# Quad_DDS.net
KiCad netlist of a schematic drawn in Altium Designer
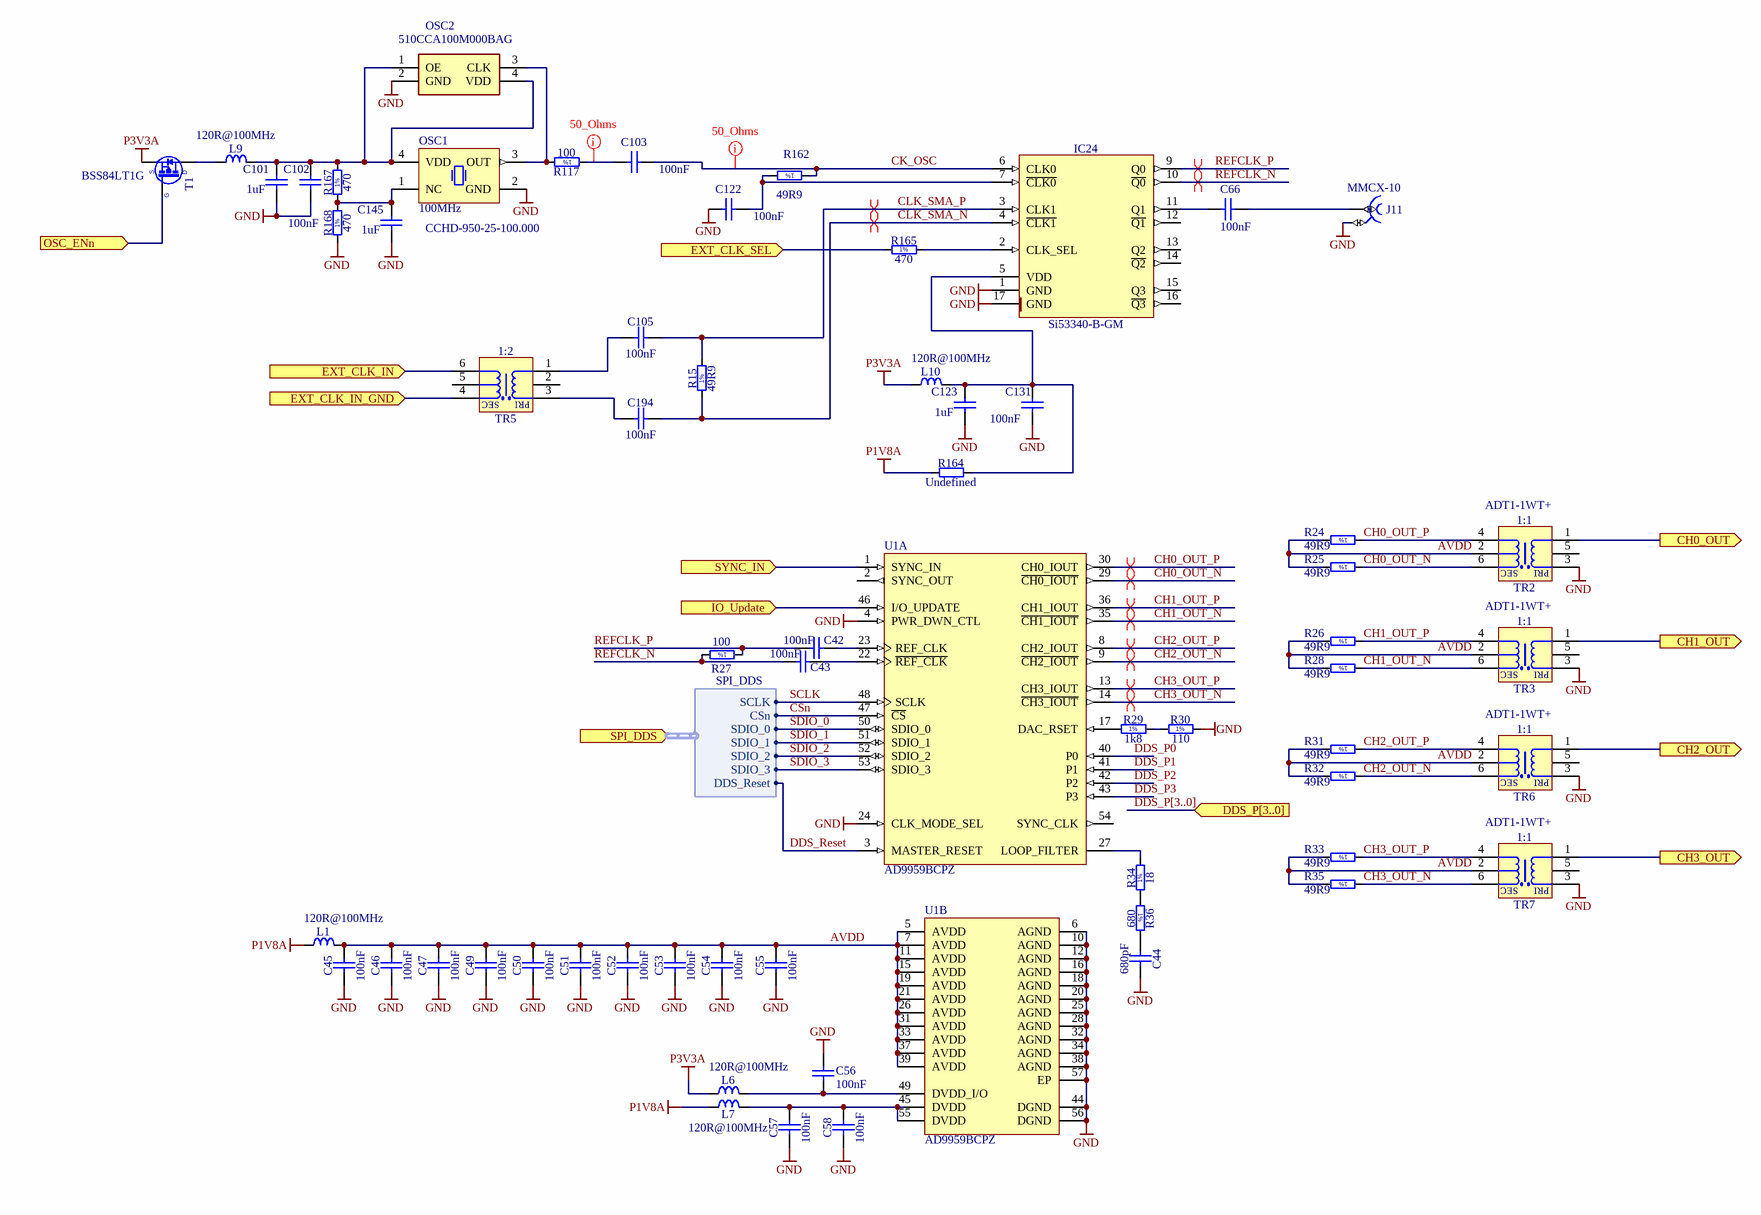
[diagram p0: Quad_DDS.SchDoc]

(export (version "E")
  (design (tool "Eeschema 10.0.6"))
  (components
    (comp (ref "C42")
      (value "100nF")
      (footprint "CAPC1005X55N")
      (description "Non-polarised capacitor")
      (fields
        (field (name "PART NUMBER") "CC0402_100NF_16V_10%_X5R")
        (field (name "VOLTAGE") "16V")
        (field (name "AUTHOR") "CERN DEM JLC")
      )
      (libsource (lib "Capacitors") (part "Capacitor - non polarized"))
    )
    (comp (ref "C43")
      (value "100nF")
      (footprint "CAPC1005X55N")
      (description "Non-polarised capacitor")
      (fields
        (field (name "PART NUMBER") "CC0402_100NF_16V_10%_X5R")
        (field (name "VOLTAGE") "16V")
        (field (name "AUTHOR") "CERN DEM JLC")
      )
      (libsource (lib "Capacitors") (part "Capacitor - non polarized"))
    )
    (comp (ref "C44")
      (value "680pF")
      (footprint "CAPC1608X87N")
      (description "Non-polarised capacitor")
      (fields
        (field (name "PART NUMBER") "CC0603_680PF_50V_5%_NP0")
        (field (name "VOLTAGE") "50V")
        (field (name "AUTHOR") "CERN DEM JLC")
      )
      (libsource (lib "Capacitors") (part "Capacitor - non polarized"))
    )
    (comp (ref "C45")
      (value "100nF")
      (footprint "CAPC1005X55N")
      (description "Non-polarised capacitor")
      (fields
        (field (name "PART NUMBER") "CC0402_100NF_16V_10%_X5R")
        (field (name "VOLTAGE") "16V")
        (field (name "AUTHOR") "CERN DEM JLC")
      )
      (libsource (lib "Capacitors") (part "Capacitor - non polarized"))
    )
    (comp (ref "C46")
      (value "100nF")
      (footprint "CAPC1005X55N")
      (description "Non-polarised capacitor")
      (fields
        (field (name "PART NUMBER") "CC0402_100NF_16V_10%_X5R")
        (field (name "VOLTAGE") "16V")
        (field (name "AUTHOR") "CERN DEM JLC")
      )
      (libsource (lib "Capacitors") (part "Capacitor - non polarized"))
    )
    (comp (ref "C47")
      (value "100nF")
      (footprint "CAPC1005X55N")
      (description "Non-polarised capacitor")
      (fields
        (field (name "PART NUMBER") "CC0402_100NF_16V_10%_X5R")
        (field (name "VOLTAGE") "16V")
        (field (name "AUTHOR") "CERN DEM JLC")
      )
      (libsource (lib "Capacitors") (part "Capacitor - non polarized"))
    )
    (comp (ref "C49")
      (value "100nF")
      (footprint "CAPC1005X55N")
      (description "Non-polarised capacitor")
      (fields
        (field (name "PART NUMBER") "CC0402_100NF_16V_10%_X5R")
        (field (name "VOLTAGE") "16V")
        (field (name "AUTHOR") "CERN DEM JLC")
      )
      (libsource (lib "Capacitors") (part "Capacitor - non polarized"))
    )
    (comp (ref "C50")
      (value "100nF")
      (footprint "CAPC1005X55N")
      (description "Non-polarised capacitor")
      (fields
        (field (name "PART NUMBER") "CC0402_100NF_16V_10%_X5R")
        (field (name "VOLTAGE") "16V")
        (field (name "AUTHOR") "CERN DEM JLC")
      )
      (libsource (lib "Capacitors") (part "Capacitor - non polarized"))
    )
    (comp (ref "C51")
      (value "100nF")
      (footprint "CAPC1005X55N")
      (description "Non-polarised capacitor")
      (fields
        (field (name "PART NUMBER") "CC0402_100NF_16V_10%_X5R")
        (field (name "VOLTAGE") "16V")
        (field (name "AUTHOR") "CERN DEM JLC")
      )
      (libsource (lib "Capacitors") (part "Capacitor - non polarized"))
    )
    (comp (ref "C52")
      (value "100nF")
      (footprint "CAPC1005X55N")
      (description "Non-polarised capacitor")
      (fields
        (field (name "PART NUMBER") "CC0402_100NF_16V_10%_X5R")
        (field (name "VOLTAGE") "16V")
        (field (name "AUTHOR") "CERN DEM JLC")
      )
      (libsource (lib "Capacitors") (part "Capacitor - non polarized"))
    )
    (comp (ref "C53")
      (value "100nF")
      (footprint "CAPC1005X55N")
      (description "Non-polarised capacitor")
      (fields
        (field (name "PART NUMBER") "CC0402_100NF_16V_10%_X5R")
        (field (name "VOLTAGE") "16V")
        (field (name "AUTHOR") "CERN DEM JLC")
      )
      (libsource (lib "Capacitors") (part "Capacitor - non polarized"))
    )
    (comp (ref "C54")
      (value "100nF")
      (footprint "CAPC1005X55N")
      (description "Non-polarised capacitor")
      (fields
        (field (name "PART NUMBER") "CC0402_100NF_16V_10%_X5R")
        (field (name "VOLTAGE") "16V")
        (field (name "AUTHOR") "CERN DEM JLC")
      )
      (libsource (lib "Capacitors") (part "Capacitor - non polarized"))
    )
    (comp (ref "C55")
      (value "100nF")
      (footprint "CAPC1005X55N")
      (description "Non-polarised capacitor")
      (fields
        (field (name "PART NUMBER") "CC0402_100NF_16V_10%_X5R")
        (field (name "VOLTAGE") "16V")
        (field (name "AUTHOR") "CERN DEM JLC")
      )
      (libsource (lib "Capacitors") (part "Capacitor - non polarized"))
    )
    (comp (ref "C56")
      (value "100nF")
      (footprint "CAPC1005X55N")
      (description "Non-polarised capacitor")
      (fields
        (field (name "PART NUMBER") "CC0402_100NF_16V_10%_X5R")
        (field (name "VOLTAGE") "16V")
        (field (name "AUTHOR") "CERN DEM JLC")
      )
      (libsource (lib "Capacitors") (part "Capacitor - non polarized"))
    )
    (comp (ref "C57")
      (value "100nF")
      (footprint "CAPC1005X55N")
      (description "Non-polarised capacitor")
      (fields
        (field (name "PART NUMBER") "CC0402_100NF_16V_10%_X5R")
        (field (name "VOLTAGE") "16V")
        (field (name "AUTHOR") "CERN DEM JLC")
      )
      (libsource (lib "Capacitors") (part "Capacitor - non polarized"))
    )
    (comp (ref "C58")
      (value "100nF")
      (footprint "CAPC1005X55N")
      (description "Non-polarised capacitor")
      (fields
        (field (name "PART NUMBER") "CC0402_100NF_16V_10%_X5R")
        (field (name "VOLTAGE") "16V")
        (field (name "AUTHOR") "CERN DEM JLC")
      )
      (libsource (lib "Capacitors") (part "Capacitor - non polarized"))
    )
    (comp (ref "C66")
      (value "100nF")
      (footprint "CAPC1005X55N")
      (description "Non-polarised capacitor")
      (fields
        (field (name "PART NUMBER") "CC0402_100NF_16V_10%_X5R")
        (field (name "VOLTAGE") "16V")
        (field (name "AUTHOR") "CERN DEM JLC")
      )
      (libsource (lib "Capacitors") (part "Capacitor - non polarized"))
    )
    (comp (ref "C101")
      (value "1uF")
      (footprint "CAPC1005X55N")
      (description "Non-polarised capacitor")
      (fields
        (field (name "PART NUMBER") "CC0402_1UF_16V_10%_X5R")
        (field (name "VOLTAGE") "16V")
        (field (name "AUTHOR") "CERN DEM JLC")
      )
      (libsource (lib "Capacitors") (part "Capacitor - non polarized"))
    )
    (comp (ref "C102")
      (value "100nF")
      (footprint "CAPC1005X55N")
      (description "Non-polarised capacitor")
      (fields
        (field (name "PART NUMBER") "CC0402_100NF_16V_10%_X5R")
        (field (name "VOLTAGE") "16V")
        (field (name "AUTHOR") "CERN DEM JLC")
      )
      (libsource (lib "Capacitors") (part "Capacitor - non polarized"))
    )
    (comp (ref "C103")
      (value "100nF")
      (footprint "CAPC1005X55N")
      (description "Non-polarised capacitor")
      (fields
        (field (name "PART NUMBER") "CC0402_100NF_16V_10%_X5R")
        (field (name "VOLTAGE") "16V")
        (field (name "AUTHOR") "CERN DEM JLC")
      )
      (libsource (lib "Capacitors") (part "Capacitor - non polarized"))
    )
    (comp (ref "C105")
      (value "100nF")
      (footprint "CAPC1005X55N")
      (description "Non-polarised capacitor")
      (fields
        (field (name "PART NUMBER") "CC0402_100NF_16V_10%_X5R")
        (field (name "VOLTAGE") "16V")
        (field (name "AUTHOR") "CERN DEM JLC")
      )
      (libsource (lib "Capacitors") (part "Capacitor - non polarized"))
    )
    (comp (ref "C122")
      (value "100nF")
      (footprint "CAPC1005X55N")
      (description "Non-polarised capacitor")
      (fields
        (field (name "PART NUMBER") "CC0402_100NF_16V_10%_X5R")
        (field (name "VOLTAGE") "16V")
        (field (name "AUTHOR") "CERN DEM JLC")
      )
      (libsource (lib "Capacitors") (part "Capacitor - non polarized"))
    )
    (comp (ref "C123")
      (value "1uF")
      (footprint "CAPC1005X55N")
      (description "Non-polarised capacitor")
      (fields
        (field (name "PART NUMBER") "CC0402_1UF_16V_10%_X5R")
        (field (name "VOLTAGE") "16V")
        (field (name "AUTHOR") "CERN DEM JLC")
      )
      (libsource (lib "Capacitors") (part "Capacitor - non polarized"))
    )
    (comp (ref "C131")
      (value "100nF")
      (footprint "CAPC1005X55N")
      (description "Non-polarised capacitor")
      (fields
        (field (name "PART NUMBER") "CC0402_100NF_16V_10%_X5R")
        (field (name "VOLTAGE") "16V")
        (field (name "AUTHOR") "CERN DEM JLC")
      )
      (libsource (lib "Capacitors") (part "Capacitor - non polarized"))
    )
    (comp (ref "C145")
      (value "1uF")
      (footprint "CAPC1005X55N")
      (description "Non-polarised capacitor")
      (fields
        (field (name "PART NUMBER") "CC0402_1UF_16V_10%_X5R")
        (field (name "VOLTAGE") "16V")
        (field (name "AUTHOR") "CERN DEM JLC")
      )
      (libsource (lib "Capacitors") (part "Capacitor - non polarized"))
    )
    (comp (ref "C194")
      (value "100nF")
      (footprint "CAPC1005X55N")
      (description "Non-polarised capacitor")
      (fields
        (field (name "PART NUMBER") "CC0402_100NF_16V_10%_X5R")
        (field (name "VOLTAGE") "16V")
        (field (name "AUTHOR") "CERN DEM JLC")
      )
      (libsource (lib "Capacitors") (part "Capacitor - non polarized"))
    )
    (comp (ref "IC24")
      (value "Si53340-B-GM")
      (footprint "QFN50P300X300X90-17N-S175")
      (description "Low-Jitter LVDS Fanout Clock Buffers, 10-Output,  Any-Input, Any-Frequency up to 1250MHz")
      (fields (field (name "MANUFACTURER") "SILICON LABS") (field (name "AUTHOR") "CERN DEM MR"))
      (libsource (lib "ICs And Semiconductors") (part "Si53340"))
    )
    (comp (ref "J11")
      (value "Coax_1Female_1Shield")
      (footprint "NINIGI_MMCX-10")
      (fields
        (field (name "PART NUMBER") "MMCX-10")
        (field (name "MANUFACTURER") "NINIGI")
        (field (name "MANUFACTURER PART NUMBER") "NINIGI MMCX-10")
        (field (name "AUTHOR") "GK")
      )
      (libsource (lib "Connectors") (part "CON_RF_MMCX"))
    )
    (comp (ref "L1")
      (value "120R@100MHz")
      (footprint "INDC1608X95N")
      (description "Inductor")
      (fields
        (field (name "PART NUMBER") "IND0603_MURATA_BLM18PG121SN1D")
        (field (name "POWER") "2A")
        (field (name "AUTHOR") "CERN DEM BC")
      )
      (libsource (lib "Inductors & Transformers") (part "Inductor"))
    )
    (comp (ref "L6")
      (value "120R@100MHz")
      (footprint "INDC1608X95N")
      (description "Inductor")
      (fields
        (field (name "PART NUMBER") "IND0603_MURATA_BLM18PG121SN1D")
        (field (name "POWER") "2A")
        (field (name "AUTHOR") "CERN DEM BC")
      )
      (libsource (lib "Inductors & Transformers") (part "Inductor"))
    )
    (comp (ref "L7")
      (value "120R@100MHz")
      (footprint "INDC1608X95N")
      (description "Inductor")
      (fields
        (field (name "PART NUMBER") "IND0603_MURATA_BLM18PG121SN1D")
        (field (name "POWER") "2A")
        (field (name "AUTHOR") "CERN DEM BC")
      )
      (libsource (lib "Inductors & Transformers") (part "Inductor"))
    )
    (comp (ref "L9")
      (value "120R@100MHz")
      (footprint "INDC1608X95N")
      (description "Inductor")
      (fields
        (field (name "PART NUMBER") "IND0603_MURATA_BLM18PG121SN1D")
        (field (name "POWER") "2A")
        (field (name "AUTHOR") "CERN DEM BC")
      )
      (libsource (lib "Inductors & Transformers") (part "Inductor"))
    )
    (comp (ref "L10")
      (value "120R@100MHz")
      (footprint "INDC1608X95N")
      (description "Inductor")
      (fields
        (field (name "PART NUMBER") "IND0603_MURATA_BLM18PG121SN1D")
        (field (name "POWER") "2A")
        (field (name "AUTHOR") "CERN DEM BC")
      )
      (libsource (lib "Inductors & Transformers") (part "Inductor"))
    )
    (comp (ref "OSC1")
      (value "100MHz")
      (footprint "OSC_CRYSTEK_CCHD-950")
      (description "100MHz low noise oscillator")
      (fields
        (field (name "PART NUMBER") "OSC_100MHZ_CRYSTEK_CCHD-950-25-100.000")
        (field (name "MANUFACTURER") "CRYSTEK CRYSTAL")
        (field (name "MANUFACTURER PART NUMBER") "CCHD-950-25-100.000")
        (field (name "AUTHOR") "GK")
      )
      (libsource (lib "LIBRARY_SCH") (part "OSC_CCHD-950"))
    )
    (comp (ref "OSC2")
      (value "510CCA100M000BAG")
      (footprint "SamacSys:510CBA49M1520BAG")
      (description "Crystal or Oscillator")
      (fields (field (name "MOUSER PART NUMBER") "634-510CCA100M000BAG"))
      (libsource (lib "*") (part "510CCA100M000BAG"))
    )
    (comp (ref "R15")
      (value "49R9")
      (footprint "RESC1005X40N")
      (description "Resistor - 1%")
      (fields
        (field (name "PART NUMBER") "R0402_49R9_1%_0.0625W_100PPM")
        (field (name "POWER") "0.0625W")
        (field (name "AUTHOR") "CERN DEM JLC")
      )
      (libsource (lib "Resistors") (part "Resistor - 1%"))
    )
    (comp (ref "R24")
      (value "49R9")
      (footprint "RESC1005X40N")
      (description "Resistor - 1%")
      (fields
        (field (name "PART NUMBER") "R0402_49R9_1%_0.0625W_100PPM")
        (field (name "POWER") "0.0625W")
        (field (name "AUTHOR") "CERN DEM JLC")
      )
      (libsource (lib "Resistors") (part "Resistor - 1%"))
    )
    (comp (ref "R25")
      (value "49R9")
      (footprint "RESC1005X40N")
      (description "Resistor - 1%")
      (fields
        (field (name "PART NUMBER") "R0402_49R9_1%_0.0625W_100PPM")
        (field (name "POWER") "0.0625W")
        (field (name "AUTHOR") "CERN DEM JLC")
      )
      (libsource (lib "Resistors") (part "Resistor - 1%"))
    )
    (comp (ref "R26")
      (value "49R9")
      (footprint "RESC1005X40N")
      (description "Resistor - 1%")
      (fields
        (field (name "PART NUMBER") "R0402_49R9_1%_0.0625W_100PPM")
        (field (name "POWER") "0.0625W")
        (field (name "AUTHOR") "CERN DEM JLC")
      )
      (libsource (lib "Resistors") (part "Resistor - 1%"))
    )
    (comp (ref "R27")
      (value "100")
      (footprint "RESC1005X40N")
      (description "Resistor - 1%")
      (fields
        (field (name "PART NUMBER") "R0402_100R_1%_0.0625W_100PPM")
        (field (name "POWER") "0.0625W")
        (field (name "AUTHOR") "CERN DEM JLC")
      )
      (libsource (lib "Resistors") (part "Resistor - 1%"))
    )
    (comp (ref "R28")
      (value "49R9")
      (footprint "RESC1005X40N")
      (description "Resistor - 1%")
      (fields
        (field (name "PART NUMBER") "R0402_49R9_1%_0.0625W_100PPM")
        (field (name "POWER") "0.0625W")
        (field (name "AUTHOR") "CERN DEM JLC")
      )
      (libsource (lib "Resistors") (part "Resistor - 1%"))
    )
    (comp (ref "R29")
      (value "1k8")
      (footprint "RESC1608X55N")
      (description "Resistor - 1%")
      (fields
        (field (name "PART NUMBER") "R0603_1K8_1%_0.1W_100PPM")
        (field (name "POWER") "0.1W")
        (field (name "AUTHOR") "CERN DEM JLC")
      )
      (libsource (lib "Resistors") (part "Resistor - 1%"))
    )
    (comp (ref "R30")
      (value "110")
      (footprint "RESC1005X40N")
      (description "Resistor - 1%")
      (fields
        (field (name "PART NUMBER") "R0402_110R_1%_0.0625W_100PPM")
        (field (name "POWER") "0.0625W")
        (field (name "AUTHOR") "CERN DEM JLC")
      )
      (libsource (lib "Resistors") (part "Resistor - 1%"))
    )
    (comp (ref "R31")
      (value "49R9")
      (footprint "RESC1005X40N")
      (description "Resistor - 1%")
      (fields
        (field (name "PART NUMBER") "R0402_49R9_1%_0.0625W_100PPM")
        (field (name "POWER") "0.0625W")
        (field (name "AUTHOR") "CERN DEM JLC")
      )
      (libsource (lib "Resistors") (part "Resistor - 1%"))
    )
    (comp (ref "R32")
      (value "49R9")
      (footprint "RESC1005X40N")
      (description "Resistor - 1%")
      (fields
        (field (name "PART NUMBER") "R0402_49R9_1%_0.0625W_100PPM")
        (field (name "POWER") "0.0625W")
        (field (name "AUTHOR") "CERN DEM JLC")
      )
      (libsource (lib "Resistors") (part "Resistor - 1%"))
    )
    (comp (ref "R33")
      (value "49R9")
      (footprint "RESC1005X40N")
      (description "Resistor - 1%")
      (fields
        (field (name "PART NUMBER") "R0402_49R9_1%_0.0625W_100PPM")
        (field (name "POWER") "0.0625W")
        (field (name "AUTHOR") "CERN DEM JLC")
      )
      (libsource (lib "Resistors") (part "Resistor - 1%"))
    )
    (comp (ref "R34")
      (value "18")
      (footprint "RESC1005X40N")
      (description "Resistor - 1%")
      (fields
        (field (name "PART NUMBER") "R0402_18R_1%_0.0625W_100PPM")
        (field (name "POWER") "0.0625W")
        (field (name "AUTHOR") "CERN DEM JLC")
      )
      (libsource (lib "Resistors") (part "Resistor - 1%"))
    )
    (comp (ref "R35")
      (value "49R9")
      (footprint "RESC1005X40N")
      (description "Resistor - 1%")
      (fields
        (field (name "PART NUMBER") "R0402_49R9_1%_0.0625W_100PPM")
        (field (name "POWER") "0.0625W")
        (field (name "AUTHOR") "CERN DEM JLC")
      )
      (libsource (lib "Resistors") (part "Resistor - 1%"))
    )
    (comp (ref "R36")
      (value "680")
      (footprint "RESC1005X40N")
      (description "Resistor - 1%")
      (fields
        (field (name "PART NUMBER") "R0402_680R_1%_0.0625W_100PPM")
        (field (name "POWER") "0.0625W")
        (field (name "AUTHOR") "CERN DEM JLC")
      )
      (libsource (lib "Resistors") (part "Resistor - 1%"))
    )
    (comp (ref "R117")
      (value "100")
      (footprint "RESC1005X40N")
      (description "Resistor - 1%")
      (fields
        (field (name "PART NUMBER") "R0402_100R_1%_0.0625W_100PPM")
        (field (name "POWER") "0.0625W")
        (field (name "AUTHOR") "CERN DEM JLC")
      )
      (libsource (lib "Resistors") (part "Resistor - 1%"))
    )
    (comp (ref "R162")
      (value "49R9")
      (footprint "RESC1005X40N")
      (description "Resistor - 1%")
      (fields
        (field (name "PART NUMBER") "R0402_49R9_1%_0.0625W_100PPM")
        (field (name "POWER") "0.0625W")
        (field (name "AUTHOR") "CERN DEM JLC")
      )
      (libsource (lib "Resistors") (part "Resistor - 1%"))
    )
    (comp (ref "R164")
      (value "Undefined")
      (footprint "RESC1608X55N")
      (description "Resistor")
      (fields (field (name "PART NUMBER") "R0603_NO-VALUE") (field (name "AUTHOR") "CERN DEM JLC"))
      (libsource (lib "Resistors") (part "Resistor"))
    )
    (comp (ref "R165")
      (value "470")
      (footprint "RESC1005X40N")
      (description "Resistor - 1%")
      (fields
        (field (name "PART NUMBER") "R0402_470R_1%_0.0625W_100PPM")
        (field (name "POWER") "0.0625W")
        (field (name "AUTHOR") "CERN DEM JLC")
      )
      (libsource (lib "Resistors") (part "Resistor - 1%"))
    )
    (comp (ref "R167")
      (value "470")
      (footprint "RESC1005X40N")
      (description "Resistor - 1%")
      (fields
        (field (name "PART NUMBER") "R0402_470R_1%_0.0625W_100PPM")
        (field (name "POWER") "0.0625W")
        (field (name "AUTHOR") "CERN DEM JLC")
      )
      (libsource (lib "Resistors") (part "Resistor - 1%"))
    )
    (comp (ref "R168")
      (value "470")
      (footprint "RESC1005X40N")
      (description "Resistor - 1%")
      (fields
        (field (name "PART NUMBER") "R0402_470R_1%_0.0625W_100PPM")
        (field (name "POWER") "0.0625W")
        (field (name "AUTHOR") "CERN DEM JLC")
      )
      (libsource (lib "Resistors") (part "Resistor - 1%"))
    )
    (comp (ref "T1")
      (value "BSS84LT1G")
      (footprint "SOT95P240X110-3N")
      (description "P-CHANNEL MOSFET WITH DIODE")
      (fields (field (name "MANUFACTURER") "ON SEMICONDUCTOR") (field (name "AUTHOR") "CERN DEM JLC"))
      (libsource (lib "ICs And Semiconductors") (part "P-MOSFET-D 1G 2S 3D"))
    )
    (comp (ref "TR2")
      (value "1:1")
      (footprint "XFMR_MINI-CIRCUITS_CD542")
      (description "75 Ohm 0.4 To 800MHz RF Transformers")
      (fields
        (field (name "PART NUMBER") "XFMR_MINI-CIRCUITS_ADT1-1WT+")
        (field (name "MANUFACTURER") "MINI-CIRCUITS")
        (field (name "MANUFACTURER PART NUMBER") "ADT1-1WT+")
        (field (name "AUTHOR") "CERN DEM JLC")
      )
      (libsource (lib "Inductors & Transformers") (part "XFMR_MINI-CIRCUITS_ADT1-1WT+"))
    )
    (comp (ref "TR3")
      (value "1:1")
      (footprint "XFMR_MINI-CIRCUITS_CD542")
      (description "75 Ohm 0.4 To 800MHz RF Transformers")
      (fields
        (field (name "PART NUMBER") "XFMR_MINI-CIRCUITS_ADT1-1WT+")
        (field (name "MANUFACTURER") "MINI-CIRCUITS")
        (field (name "MANUFACTURER PART NUMBER") "ADT1-1WT+")
        (field (name "AUTHOR") "CERN DEM JLC")
      )
      (libsource (lib "Inductors & Transformers") (part "XFMR_MINI-CIRCUITS_ADT1-1WT+"))
    )
    (comp (ref "TR5")
      (value "1:2")
      (footprint "XFMR_MINI-CIRCUITS_CD542")
      (description "50 Ohms 0.4 To 450MHz RF Transformer")
      (fields
        (field (name "PART NUMBER") "XFMR_MINI-CIRCUITS_ADT2-1T+")
        (field (name "MANUFACTURER") "MINI-CIRCUITS")
        (field (name "AUTHOR") "CERN DEM MR")
      )
      (libsource (lib "Inductors & Transformers") (part "XFMR_MINI-CIRCUITS_ADT2-1T-1P+"))
    )
    (comp (ref "TR6")
      (value "1:1")
      (footprint "XFMR_MINI-CIRCUITS_CD542")
      (description "75 Ohm 0.4 To 800MHz RF Transformers")
      (fields
        (field (name "PART NUMBER") "XFMR_MINI-CIRCUITS_ADT1-1WT+")
        (field (name "MANUFACTURER") "MINI-CIRCUITS")
        (field (name "MANUFACTURER PART NUMBER") "ADT1-1WT+")
        (field (name "AUTHOR") "CERN DEM JLC")
      )
      (libsource (lib "Inductors & Transformers") (part "XFMR_MINI-CIRCUITS_ADT1-1WT+"))
    )
    (comp (ref "TR7")
      (value "1:1")
      (footprint "XFMR_MINI-CIRCUITS_CD542")
      (description "75 Ohm 0.4 To 800MHz RF Transformers")
      (fields
        (field (name "PART NUMBER") "XFMR_MINI-CIRCUITS_ADT1-1WT+")
        (field (name "MANUFACTURER") "MINI-CIRCUITS")
        (field (name "MANUFACTURER PART NUMBER") "ADT1-1WT+")
        (field (name "AUTHOR") "CERN DEM JLC")
      )
      (libsource (lib "Inductors & Transformers") (part "XFMR_MINI-CIRCUITS_ADT1-1WT+"))
    )
    (comp (ref "U1")
      (value "AD9959BCPZ")
      (footprint "ADI-CP-56-1_M")
      (description "4-Channel, 500 MSPS DDS with 10-Bit DACs, Serial, CP-56-1, 260 Tray, Pb-Free")
      (libsource (lib "Altium Content Vault") (part "ADI-AD9959-CP-56-1"))
    )
  )
  (nets
    (net (code "2") (name "/AVDD") (class "Default")
      (node (ref "C45") (pin "2") (pinfunction "2_2") (pintype "passive"))
      (node (ref "C46") (pin "2") (pinfunction "2_2") (pintype "passive"))
      (node (ref "C47") (pin "2") (pinfunction "2_2") (pintype "passive"))
      (node (ref "C49") (pin "2") (pinfunction "2_2") (pintype "passive"))
      (node (ref "C50") (pin "2") (pinfunction "2_2") (pintype "passive"))
      (node (ref "C51") (pin "2") (pinfunction "2_2") (pintype "passive"))
      (node (ref "C52") (pin "2") (pinfunction "2_2") (pintype "passive"))
      (node (ref "C53") (pin "2") (pinfunction "2_2") (pintype "passive"))
      (node (ref "C54") (pin "2") (pinfunction "2_2") (pintype "passive"))
      (node (ref "C55") (pin "2") (pinfunction "2_2") (pintype "passive"))
      (node (ref "L1") (pin "1") (pinfunction "1_1") (pintype "passive"))
      (node (ref "R24") (pin "2") (pinfunction "2_2") (pintype "passive"))
      (node (ref "R25") (pin "2") (pinfunction "2_2") (pintype "passive"))
      (node (ref "R26") (pin "2") (pinfunction "2_2") (pintype "passive"))
      (node (ref "R28") (pin "2") (pinfunction "2_2") (pintype "passive"))
      (node (ref "R31") (pin "2") (pinfunction "2_2") (pintype "passive"))
      (node (ref "R32") (pin "2") (pinfunction "2_2") (pintype "passive"))
      (node (ref "R33") (pin "2") (pinfunction "2_2") (pintype "passive"))
      (node (ref "R35") (pin "2") (pinfunction "2_2") (pintype "passive"))
      (node (ref "TR2") (pin "2") (pinfunction "SCT_2") (pintype "passive"))
      (node (ref "TR3") (pin "2") (pinfunction "SCT_2") (pintype "passive"))
      (node (ref "TR6") (pin "2") (pinfunction "SCT_2") (pintype "passive"))
      (node (ref "TR7") (pin "2") (pinfunction "SCT_2") (pintype "passive"))
      (node (ref "U1") (pin "11") (pinfunction "AVDD_11") (pintype "power_in"))
      (node (ref "U1") (pin "15") (pinfunction "AVDD_15") (pintype "power_in"))
      (node (ref "U1") (pin "19") (pinfunction "AVDD_19") (pintype "power_in"))
      (node (ref "U1") (pin "21") (pinfunction "AVDD_21") (pintype "power_in"))
      (node (ref "U1") (pin "26") (pinfunction "AVDD_26") (pintype "power_in"))
      (node (ref "U1") (pin "31") (pinfunction "AVDD_31") (pintype "power_in"))
      (node (ref "U1") (pin "33") (pinfunction "AVDD_33") (pintype "power_in"))
      (node (ref "U1") (pin "37") (pinfunction "AVDD_37") (pintype "power_in"))
      (node (ref "U1") (pin "39") (pinfunction "AVDD_39") (pintype "power_in"))
      (node (ref "U1") (pin "5") (pinfunction "AVDD_5") (pintype "power_in"))
      (node (ref "U1") (pin "7") (pinfunction "AVDD_7") (pintype "power_in"))
    )
    (net (code "3") (name "/CH0_OUT") (class "Default")
      (node (ref "TR2") (pin "1") (pinfunction "P_1") (pintype "passive"))
    )
    (net (code "4") (name "/CH0_OUT_N") (class "Default")
      (node (ref "R25") (pin "1") (pinfunction "1_1") (pintype "passive"))
      (node (ref "TR2") (pin "6") (pinfunction "SDOT_6") (pintype "passive"))
      (node (ref "U1") (pin "29") (pinfunction "~{CH0_IOUT}_29") (pintype "output"))
    )
    (net (code "5") (name "/CH0_OUT_P") (class "Default")
      (node (ref "R24") (pin "1") (pinfunction "1_1") (pintype "passive"))
      (node (ref "TR2") (pin "4") (pinfunction "S_4") (pintype "passive"))
      (node (ref "U1") (pin "30") (pinfunction "CH0_IOUT_30") (pintype "output"))
    )
    (net (code "6") (name "/CH1_OUT") (class "Default")
      (node (ref "TR3") (pin "1") (pinfunction "P_1") (pintype "passive"))
    )
    (net (code "7") (name "/CH1_OUT_N") (class "Default")
      (node (ref "R28") (pin "1") (pinfunction "1_1") (pintype "passive"))
      (node (ref "TR3") (pin "6") (pinfunction "SDOT_6") (pintype "passive"))
      (node (ref "U1") (pin "35") (pinfunction "~{CH1_IOUT}_35") (pintype "output"))
    )
    (net (code "8") (name "/CH1_OUT_P") (class "Default")
      (node (ref "R26") (pin "1") (pinfunction "1_1") (pintype "passive"))
      (node (ref "TR3") (pin "4") (pinfunction "S_4") (pintype "passive"))
      (node (ref "U1") (pin "36") (pinfunction "CH1_IOUT_36") (pintype "output"))
    )
    (net (code "9") (name "/CH2_OUT") (class "Default")
      (node (ref "TR6") (pin "1") (pinfunction "P_1") (pintype "passive"))
    )
    (net (code "10") (name "/CH2_OUT_N") (class "Default")
      (node (ref "R32") (pin "1") (pinfunction "1_1") (pintype "passive"))
      (node (ref "TR6") (pin "6") (pinfunction "SDOT_6") (pintype "passive"))
      (node (ref "U1") (pin "9") (pinfunction "~{CH2_IOUT}_9") (pintype "output"))
    )
    (net (code "11") (name "/CH2_OUT_P") (class "Default")
      (node (ref "R31") (pin "1") (pinfunction "1_1") (pintype "passive"))
      (node (ref "TR6") (pin "4") (pinfunction "S_4") (pintype "passive"))
      (node (ref "U1") (pin "8") (pinfunction "CH2_IOUT_8") (pintype "output"))
    )
    (net (code "12") (name "/CH3_OUT") (class "Default")
      (node (ref "TR7") (pin "1") (pinfunction "P_1") (pintype "passive"))
    )
    (net (code "13") (name "/CH3_OUT_N") (class "Default")
      (node (ref "R35") (pin "1") (pinfunction "1_1") (pintype "passive"))
      (node (ref "TR7") (pin "6") (pinfunction "SDOT_6") (pintype "passive"))
      (node (ref "U1") (pin "14") (pinfunction "~{CH3_IOUT}_14") (pintype "output"))
    )
    (net (code "14") (name "/CH3_OUT_P") (class "Default")
      (node (ref "R33") (pin "1") (pinfunction "1_1") (pintype "passive"))
      (node (ref "TR7") (pin "4") (pinfunction "S_4") (pintype "passive"))
      (node (ref "U1") (pin "13") (pinfunction "CH3_IOUT_13") (pintype "output"))
    )
    (net (code "15") (name "/CK_OSC") (class "Default")
      (node (ref "C103") (pin "1") (pinfunction "1_1") (pintype "passive"))
      (node (ref "IC24") (pin "6") (pinfunction "CLK0_6") (pintype "input"))
      (node (ref "R162") (pin "1") (pinfunction "1_1") (pintype "passive"))
    )
    (net (code "16") (name "/CLK_SMA_N") (class "Default")
      (node (ref "C194") (pin "2") (pinfunction "2_2") (pintype "passive"))
      (node (ref "IC24") (pin "4") (pinfunction "~{CLK1}_4") (pintype "input"))
      (node (ref "R15") (pin "1") (pinfunction "1_1") (pintype "passive"))
    )
    (net (code "17") (name "/CLK_SMA_P") (class "Default")
      (node (ref "C105") (pin "2") (pinfunction "2_2") (pintype "passive"))
      (node (ref "IC24") (pin "3") (pinfunction "CLK1_3") (pintype "input"))
      (node (ref "R15") (pin "2") (pinfunction "2_2") (pintype "passive"))
    )
    (net (code "18") (name "/CSn") (class "Default")
      (node (ref "U1") (pin "47") (pinfunction "~{CS}_47") (pintype "input"))
    )
    (net (code "19") (name "/DDS_P0") (class "Default")
      (node (ref "U1") (pin "40") (pinfunction "P0_40") (pintype "input"))
    )
    (net (code "20") (name "/DDS_P1") (class "Default")
      (node (ref "U1") (pin "41") (pinfunction "P1_41") (pintype "input"))
    )
    (net (code "21") (name "/DDS_P2") (class "Default")
      (node (ref "U1") (pin "42") (pinfunction "P2_42") (pintype "input"))
    )
    (net (code "22") (name "/DDS_P3") (class "Default")
      (node (ref "U1") (pin "43") (pinfunction "P3_43") (pintype "input"))
    )
    (net (code "24") (name "/DDS_Reset") (class "Default")
      (node (ref "U1") (pin "3") (pinfunction "MASTER_RESET_3") (pintype "input"))
    )
    (net (code "25") (name "/EXT_CLK_IN") (class "Default")
      (node (ref "TR5") (pin "6") (pinfunction "SDOT_6") (pintype "passive"))
    )
    (net (code "26") (name "/EXT_CLK_IN_GND") (class "Default")
      (node (ref "TR5") (pin "4") (pinfunction "S_4") (pintype "passive"))
    )
    (net (code "27") (name "/EXT_CLK_SEL") (class "Default")
      (node (ref "R165") (pin "1") (pinfunction "1_1") (pintype "passive"))
    )
    (net (code "28") (name "/IO_Update") (class "Default")
      (node (ref "U1") (pin "46") (pinfunction "I/O_UPDATE_46") (pintype "input"))
    )
    (net (code "29") (name "/OSC_ENn") (class "Default")
      (node (ref "T1") (pin "1") (pinfunction "G_1") (pintype "passive"))
    )
    (net (code "30") (name "/REFCLK_N") (class "Default")
      (node (ref "C43") (pin "2") (pinfunction "2_2") (pintype "passive"))
      (node (ref "IC24") (pin "10") (pinfunction "~{Q0}_10") (pintype "output"))
      (node (ref "R27") (pin "2") (pinfunction "2_2") (pintype "passive"))
    )
    (net (code "31") (name "/REFCLK_P") (class "Default")
      (node (ref "C42") (pin "2") (pinfunction "2_2") (pintype "passive"))
      (node (ref "IC24") (pin "9") (pinfunction "Q0_9") (pintype "output"))
      (node (ref "R27") (pin "1") (pinfunction "1_1") (pintype "passive"))
    )
    (net (code "32") (name "/SCLK") (class "Default")
      (node (ref "U1") (pin "48") (pinfunction "SCLK_48") (pintype "input"))
    )
    (net (code "33") (name "/SDIO_0") (class "Default")
      (node (ref "U1") (pin "50") (pinfunction "SDIO_0_50") (pintype "bidirectional"))
    )
    (net (code "34") (name "/SDIO_1") (class "Default")
      (node (ref "U1") (pin "51") (pinfunction "SDIO_1_51") (pintype "bidirectional"))
    )
    (net (code "35") (name "/SDIO_2") (class "Default")
      (node (ref "U1") (pin "52") (pinfunction "SDIO_2_52") (pintype "bidirectional"))
    )
    (net (code "36") (name "/SDIO_3") (class "Default")
      (node (ref "U1") (pin "53") (pinfunction "SDIO_3_53") (pintype "bidirectional"))
    )
    (net (code "37") (name "/SYNC_IN") (class "Default")
      (node (ref "U1") (pin "1") (pinfunction "SYNC_IN_1") (pintype "input"))
    )
    (net (code "39") (name "GND") (class "Default")
      (node (ref "C101") (pin "1") (pinfunction "1_1") (pintype "passive"))
      (node (ref "C102") (pin "1") (pinfunction "1_1") (pintype "passive"))
      (node (ref "C122") (pin "2") (pinfunction "2_2") (pintype "passive"))
      (node (ref "C123") (pin "1") (pinfunction "1_1") (pintype "passive"))
      (node (ref "C131") (pin "1") (pinfunction "1_1") (pintype "passive"))
      (node (ref "C145") (pin "1") (pinfunction "1_1") (pintype "passive"))
      (node (ref "C44") (pin "2") (pinfunction "2_2") (pintype "passive"))
      (node (ref "C45") (pin "1") (pinfunction "1_1") (pintype "passive"))
      (node (ref "C46") (pin "1") (pinfunction "1_1") (pintype "passive"))
      (node (ref "C47") (pin "1") (pinfunction "1_1") (pintype "passive"))
      (node (ref "C49") (pin "1") (pinfunction "1_1") (pintype "passive"))
      (node (ref "C50") (pin "1") (pinfunction "1_1") (pintype "passive"))
      (node (ref "C51") (pin "1") (pinfunction "1_1") (pintype "passive"))
      (node (ref "C52") (pin "1") (pinfunction "1_1") (pintype "passive"))
      (node (ref "C53") (pin "1") (pinfunction "1_1") (pintype "passive"))
      (node (ref "C54") (pin "1") (pinfunction "1_1") (pintype "passive"))
      (node (ref "C55") (pin "1") (pinfunction "1_1") (pintype "passive"))
      (node (ref "C56") (pin "1") (pinfunction "1_1") (pintype "passive"))
      (node (ref "C57") (pin "1") (pinfunction "1_1") (pintype "passive"))
      (node (ref "C58") (pin "1") (pinfunction "1_1") (pintype "passive"))
      (node (ref "IC24") (pin "1") (pinfunction "GND_1") (pintype "power_in"))
      (node (ref "IC24") (pin "17") (pinfunction "GND_17") (pintype "power_in"))
      (node (ref "J11") (pin "2") (pinfunction "2_2") (pintype "bidirectional"))
      (node (ref "OSC1") (pin "2") (pinfunction "GND_2") (pintype "power_in"))
      (node (ref "OSC2") (pin "2") (pinfunction "GND_2") (pintype "passive"))
      (node (ref "R168") (pin "1") (pinfunction "1_1") (pintype "passive"))
      (node (ref "R30") (pin "2") (pinfunction "2_2") (pintype "passive"))
      (node (ref "TR2") (pin "3") (pinfunction "PDOT_3") (pintype "passive"))
      (node (ref "TR3") (pin "3") (pinfunction "PDOT_3") (pintype "passive"))
      (node (ref "TR6") (pin "3") (pinfunction "PDOT_3") (pintype "passive"))
      (node (ref "TR7") (pin "3") (pinfunction "PDOT_3") (pintype "passive"))
      (node (ref "U1") (pin "10") (pinfunction "AGND_10") (pintype "power_in"))
      (node (ref "U1") (pin "12") (pinfunction "AGND_12") (pintype "power_in"))
      (node (ref "U1") (pin "16") (pinfunction "AGND_16") (pintype "power_in"))
      (node (ref "U1") (pin "18") (pinfunction "AGND_18") (pintype "power_in"))
      (node (ref "U1") (pin "20") (pinfunction "AGND_20") (pintype "power_in"))
      (node (ref "U1") (pin "24") (pinfunction "CLK_MODE_SEL_24") (pintype "input"))
      (node (ref "U1") (pin "25") (pinfunction "AGND_25") (pintype "power_in"))
      (node (ref "U1") (pin "28") (pinfunction "AGND_28") (pintype "power_in"))
      (node (ref "U1") (pin "32") (pinfunction "AGND_32") (pintype "power_in"))
      (node (ref "U1") (pin "34") (pinfunction "AGND_34") (pintype "power_in"))
      (node (ref "U1") (pin "38") (pinfunction "AGND_38") (pintype "power_in"))
      (node (ref "U1") (pin "4") (pinfunction "PWR_DWN_CTL_4") (pintype "input"))
      (node (ref "U1") (pin "44") (pinfunction "DGND_44") (pintype "power_in"))
      (node (ref "U1") (pin "56") (pinfunction "DGND_56") (pintype "power_in"))
      (node (ref "U1") (pin "57") (pinfunction "EP_57") (pintype "power_in"))
      (node (ref "U1") (pin "6") (pinfunction "AGND_6") (pintype "power_in"))
    )
    (net (code "40") (name "Net-(C44-Pad1)") (class "Default")
      (node (ref "C44") (pin "1") (pinfunction "1_1") (pintype "passive"))
      (node (ref "R36") (pin "2") (pinfunction "2_2") (pintype "passive"))
    )
    (net (code "41") (name "Net-(C57-Pad2)") (class "Default")
      (node (ref "C57") (pin "2") (pinfunction "2_2") (pintype "passive"))
      (node (ref "C58") (pin "2") (pinfunction "2_2") (pintype "passive"))
      (node (ref "L7") (pin "1") (pinfunction "1_1") (pintype "passive"))
      (node (ref "U1") (pin "45") (pinfunction "DVDD_45") (pintype "power_in"))
      (node (ref "U1") (pin "55") (pinfunction "DVDD_55") (pintype "power_in"))
    )
    (net (code "42") (name "Net-(C66-Pad1)") (class "Default")
      (node (ref "C66") (pin "1") (pinfunction "1_1") (pintype "passive"))
      (node (ref "J11") (pin "1") (pinfunction "1_1") (pintype "bidirectional"))
    )
    (net (code "43") (name "Net-(C103-Pad2)") (class "Default")
      (node (ref "C103") (pin "2") (pinfunction "2_2") (pintype "passive"))
      (node (ref "R117") (pin "1") (pinfunction "1_1") (pintype "passive"))
    )
    (net (code "44") (name "Net-(IC24-CLK_SEL)") (class "Default")
      (node (ref "IC24") (pin "2") (pinfunction "CLK_SEL_2") (pintype "input"))
      (node (ref "R165") (pin "2") (pinfunction "2_2") (pintype "passive"))
    )
    (net (code "45") (name "Net-(IC24-Q1)") (class "Default")
      (node (ref "C66") (pin "2") (pinfunction "2_2") (pintype "passive"))
      (node (ref "IC24") (pin "11") (pinfunction "Q1_11") (pintype "output"))
    )
    (net (code "46") (name "Net-(IC24-VDD)") (class "Default")
      (node (ref "C123") (pin "2") (pinfunction "2_2") (pintype "passive"))
      (node (ref "C131") (pin "2") (pinfunction "2_2") (pintype "passive"))
      (node (ref "IC24") (pin "5") (pinfunction "VDD_5") (pintype "power_in"))
      (node (ref "L10") (pin "1") (pinfunction "1_1") (pintype "passive"))
      (node (ref "R164") (pin "2") (pinfunction "2_2") (pintype "passive"))
    )
    (net (code "47") (name "Net-(IC24-~{CLK0})") (class "Default")
      (node (ref "C122") (pin "1") (pinfunction "1_1") (pintype "passive"))
      (node (ref "IC24") (pin "7") (pinfunction "~{CLK0}_7") (pintype "input"))
      (node (ref "R162") (pin "2") (pinfunction "2_2") (pintype "passive"))
    )
    (net (code "48") (name "Net-(OSC1-NC)") (class "Default")
      (node (ref "C145") (pin "2") (pinfunction "2_2") (pintype "passive"))
      (node (ref "OSC1") (pin "1") (pinfunction "NC_1") (pintype "passive"))
      (node (ref "R167") (pin "1") (pinfunction "1_1") (pintype "passive"))
      (node (ref "R168") (pin "2") (pinfunction "2_2") (pintype "passive"))
    )
    (net (code "49") (name "Net-(OSC1-OUT)") (class "Default")
      (node (ref "OSC1") (pin "3") (pinfunction "OUT_3") (pintype "output"))
      (node (ref "OSC2") (pin "3") (pinfunction "CLK_3") (pintype "passive"))
      (node (ref "R117") (pin "2") (pinfunction "2_2") (pintype "passive"))
    )
    (net (code "50") (name "Net-(OSC1-VDD)") (class "Default")
      (node (ref "C101") (pin "2") (pinfunction "2_2") (pintype "passive"))
      (node (ref "C102") (pin "2") (pinfunction "2_2") (pintype "passive"))
      (node (ref "L9") (pin "1") (pinfunction "1_1") (pintype "passive"))
      (node (ref "OSC1") (pin "4") (pinfunction "VDD_4") (pintype "power_in"))
      (node (ref "OSC2") (pin "1") (pinfunction "OE_1") (pintype "passive"))
      (node (ref "OSC2") (pin "4") (pinfunction "VDD_4") (pintype "passive"))
      (node (ref "R167") (pin "2") (pinfunction "2_2") (pintype "passive"))
    )
    (net (code "51") (name "Net-(R29-Pad2)") (class "Default")
      (node (ref "R29") (pin "2") (pinfunction "2_2") (pintype "passive"))
      (node (ref "R30") (pin "1") (pinfunction "1_1") (pintype "passive"))
    )
    (net (code "52") (name "Net-(R34-Pad1)") (class "Default")
      (node (ref "R34") (pin "1") (pinfunction "1_1") (pintype "passive"))
      (node (ref "R36") (pin "1") (pinfunction "1_1") (pintype "passive"))
    )
    (net (code "53") (name "Net-(T1-D)") (class "Default")
      (node (ref "L9") (pin "2") (pinfunction "2_2") (pintype "passive"))
      (node (ref "T1") (pin "3") (pinfunction "D_3") (pintype "passive"))
    )
    (net (code "54") (name "Net-(TR5-P)") (class "Default")
      (node (ref "C105") (pin "1") (pinfunction "1_1") (pintype "passive"))
      (node (ref "TR5") (pin "1") (pinfunction "P_1") (pintype "passive"))
    )
    (net (code "55") (name "Net-(TR5-PDOT)") (class "Default")
      (node (ref "C194") (pin "1") (pinfunction "1_1") (pintype "passive"))
      (node (ref "TR5") (pin "3") (pinfunction "PDOT_3") (pintype "passive"))
    )
    (net (code "56") (name "Net-(U1A-DAC_RSET)") (class "Default")
      (node (ref "R29") (pin "1") (pinfunction "1_1") (pintype "passive"))
      (node (ref "U1") (pin "17") (pinfunction "DAC_RSET_17") (pintype "input"))
    )
    (net (code "57") (name "Net-(U1A-LOOP_FILTER)") (class "Default")
      (node (ref "R34") (pin "2") (pinfunction "2_2") (pintype "passive"))
      (node (ref "U1") (pin "27") (pinfunction "LOOP_FILTER_27") (pintype "passive"))
    )
    (net (code "58") (name "Net-(U1A-REF_CLK)") (class "Default")
      (node (ref "C42") (pin "1") (pinfunction "1_1") (pintype "passive"))
      (node (ref "U1") (pin "23") (pinfunction "REF_CLK_23") (pintype "input"))
    )
    (net (code "59") (name "Net-(U1A-~{REF_CLK})") (class "Default")
      (node (ref "C43") (pin "1") (pinfunction "1_1") (pintype "passive"))
      (node (ref "U1") (pin "22") (pinfunction "~{REF_CLK}_22") (pintype "input"))
    )
    (net (code "60") (name "Net-(U1B-DVDD_I{slash}O)") (class "Default")
      (node (ref "C56") (pin "2") (pinfunction "2_2") (pintype "passive"))
      (node (ref "L6") (pin "1") (pinfunction "1_1") (pintype "passive"))
      (node (ref "U1") (pin "49") (pinfunction "DVDD_I/O_49") (pintype "power_in"))
    )
    (net (code "61") (name "P1V8A") (class "Default")
      (node (ref "L1") (pin "2") (pinfunction "2_2") (pintype "passive"))
      (node (ref "L7") (pin "2") (pinfunction "2_2") (pintype "passive"))
      (node (ref "R164") (pin "1") (pinfunction "1_1") (pintype "passive"))
    )
    (net (code "62") (name "P3V3A") (class "Default")
      (node (ref "L10") (pin "2") (pinfunction "2_2") (pintype "passive"))
      (node (ref "L6") (pin "2") (pinfunction "2_2") (pintype "passive"))
      (node (ref "T1") (pin "2") (pinfunction "S_2") (pintype "passive"))
    )
    (net (code "63") (name "unconnected-(IC24-Q2-Pad13)") (class "Default")
      (node (ref "IC24") (pin "13") (pinfunction "Q2_13") (pintype "output"))
    )
    (net (code "64") (name "unconnected-(IC24-Q3-Pad15)") (class "Default")
      (node (ref "IC24") (pin "15") (pinfunction "Q3_15") (pintype "output"))
    )
    (net (code "65") (name "unconnected-(IC24-~{Q1}-Pad12)") (class "Default")
      (node (ref "IC24") (pin "12") (pinfunction "~{Q1}_12") (pintype "output"))
    )
    (net (code "66") (name "unconnected-(IC24-~{Q2}-Pad14)") (class "Default")
      (node (ref "IC24") (pin "14") (pinfunction "~{Q2}_14") (pintype "output"))
    )
    (net (code "67") (name "unconnected-(IC24-~{Q3}-Pad16)") (class "Default")
      (node (ref "IC24") (pin "16") (pinfunction "~{Q3}_16") (pintype "output"))
    )
    (net (code "68") (name "unconnected-(TR2-NC-Pad5)") (class "Default")
      (node (ref "TR2") (pin "5") (pinfunction "NC_5") (pintype "passive"))
    )
    (net (code "69") (name "unconnected-(TR3-NC-Pad5)") (class "Default")
      (node (ref "TR3") (pin "5") (pinfunction "NC_5") (pintype "passive"))
    )
    (net (code "70") (name "unconnected-(TR5-NC-Pad2)") (class "Default")
      (node (ref "TR5") (pin "2") (pinfunction "NC_2") (pintype "passive"))
    )
    (net (code "71") (name "unconnected-(TR5-SCT-Pad5)") (class "Default")
      (node (ref "TR5") (pin "5") (pinfunction "SCT_5") (pintype "passive"))
    )
    (net (code "72") (name "unconnected-(TR6-NC-Pad5)") (class "Default")
      (node (ref "TR6") (pin "5") (pinfunction "NC_5") (pintype "passive"))
    )
    (net (code "73") (name "unconnected-(TR7-NC-Pad5)") (class "Default")
      (node (ref "TR7") (pin "5") (pinfunction "NC_5") (pintype "passive"))
    )
    (net (code "74") (name "unconnected-(U1A-SYNC_CLK-Pad54)") (class "Default")
      (node (ref "U1") (pin "54") (pinfunction "SYNC_CLK_54") (pintype "output"))
    )
    (net (code "75") (name "unconnected-(U1A-SYNC_OUT-Pad2)") (class "Default")
      (node (ref "U1") (pin "2") (pinfunction "SYNC_OUT_2") (pintype "output"))
    )
  )
)
